# 4-LightSensor.net
KiCad netlist of a schematic drawn in Altium Designer
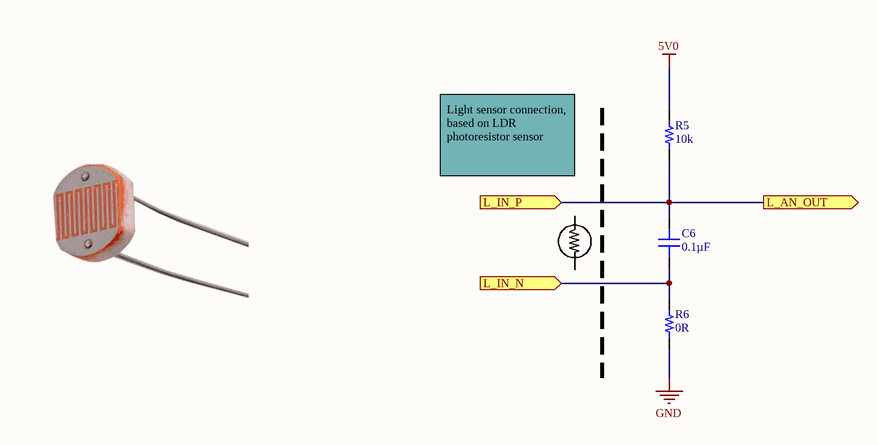
[diagram p0: 4-LightSensor.SchDoc]

(export (version "E")
  (design (tool "Eeschema 10.0.6"))
  (components
    (comp (ref "C6")
      (value "0.1µF")
      (footprint "CAP 0805_2012")
      (description "CAP CER 0.1UF 50V X7R 0805")
      (fields (field (name "PART NUMBER") "C0805C104M5RACAUTO") (field (name "MANUFACTURER") "KEMET"))
      (libsource (lib "Celestial Altium Library - altium_library") (part "Capacitor"))
    )
    (comp (ref "R5")
      (value "10k")
      (footprint "RES 0805_2012")
      (description "RES SMD 1.47K OHM 1% 1/8W 0805")
      (fields (field (name "PART NUMBER") "RC0805FR-071K47L") (field (name "MANUFACTURER") "Yageo"))
      (libsource (lib "Celestial Altium Library - altium_library") (part "Resistor"))
    )
    (comp (ref "R6")
      (value "0R")
      (footprint "RES 0805_2012")
      (description "RES SMD 1.47K OHM 1% 1/8W 0805")
      (fields (field (name "PART NUMBER") "RC0805FR-071K47L") (field (name "MANUFACTURER") "Yageo"))
      (libsource (lib "Celestial Altium Library - altium_library") (part "Resistor"))
    )
  )
  (nets
    (net (code "1") (name "/L_AN_OUT") (class "Default")
      (node (ref "C6") (pin "2") (pinfunction "2_2") (pintype "passive"))
      (node (ref "R5") (pin "1") (pinfunction "1_1") (pintype "passive"))
    )
    (net (code "2") (name "/L_IN_N") (class "Default")
      (node (ref "C6") (pin "1") (pinfunction "1_1") (pintype "passive"))
      (node (ref "R6") (pin "2") (pinfunction "2_2") (pintype "passive"))
    )
    (net (code "3") (name "5V0") (class "Default")
      (node (ref "R5") (pin "2") (pinfunction "2_2") (pintype "passive"))
    )
    (net (code "4") (name "GND") (class "Default")
      (node (ref "R6") (pin "1") (pinfunction "1_1") (pintype "passive"))
    )
  )
)
